# breakout-18.net
KiCad netlist of a schematic drawn in EAGLE
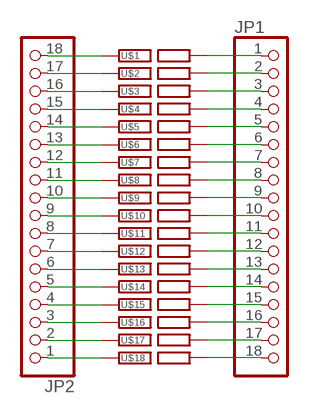
[diagram p0: schematic, sheet 1]

(export (version "E")
  (design (tool "Eeschema 10.0.6"))
  (components
    (comp (ref "JP1")
      (value "PINHD-1X18")
      (footprint "eagle-import:1X18")
      (libsource (lib "eagle-import") (part "PINHD-1X18"))
    )
    (comp (ref "JP2")
      (value "PINHD-1X18")
      (footprint "eagle-import:1X18")
      (libsource (lib "eagle-import") (part "PINHD-1X18"))
    )
    (comp (ref "U$1")
      (value "RAILSEP")
      (footprint "eagle-import:RAIL")
      (libsource (lib "eagle-import") (part "RAILSEP"))
    )
    (comp (ref "U$2")
      (value "RAILSEP")
      (footprint "eagle-import:RAIL")
      (libsource (lib "eagle-import") (part "RAILSEP"))
    )
    (comp (ref "U$3")
      (value "RAILSEP")
      (footprint "eagle-import:RAIL")
      (libsource (lib "eagle-import") (part "RAILSEP"))
    )
    (comp (ref "U$4")
      (value "RAILSEP")
      (footprint "eagle-import:RAIL")
      (libsource (lib "eagle-import") (part "RAILSEP"))
    )
    (comp (ref "U$5")
      (value "RAILSEP")
      (footprint "eagle-import:RAIL")
      (libsource (lib "eagle-import") (part "RAILSEP"))
    )
    (comp (ref "U$6")
      (value "RAILSEP")
      (footprint "eagle-import:RAIL")
      (libsource (lib "eagle-import") (part "RAILSEP"))
    )
    (comp (ref "U$7")
      (value "RAILSEP")
      (footprint "eagle-import:RAIL")
      (libsource (lib "eagle-import") (part "RAILSEP"))
    )
    (comp (ref "U$8")
      (value "RAILSEP")
      (footprint "eagle-import:RAIL")
      (libsource (lib "eagle-import") (part "RAILSEP"))
    )
    (comp (ref "U$9")
      (value "RAILSEP")
      (footprint "eagle-import:RAIL")
      (libsource (lib "eagle-import") (part "RAILSEP"))
    )
    (comp (ref "U$10")
      (value "RAILSEP")
      (footprint "eagle-import:RAIL")
      (libsource (lib "eagle-import") (part "RAILSEP"))
    )
    (comp (ref "U$11")
      (value "RAILSEP")
      (footprint "eagle-import:RAIL")
      (libsource (lib "eagle-import") (part "RAILSEP"))
    )
    (comp (ref "U$12")
      (value "RAILSEP")
      (footprint "eagle-import:RAIL")
      (libsource (lib "eagle-import") (part "RAILSEP"))
    )
    (comp (ref "U$13")
      (value "RAILSEP")
      (footprint "eagle-import:RAIL")
      (libsource (lib "eagle-import") (part "RAILSEP"))
    )
    (comp (ref "U$14")
      (value "RAILSEP")
      (footprint "eagle-import:RAIL")
      (libsource (lib "eagle-import") (part "RAILSEP"))
    )
    (comp (ref "U$15")
      (value "RAILSEP")
      (footprint "eagle-import:RAIL")
      (libsource (lib "eagle-import") (part "RAILSEP"))
    )
    (comp (ref "U$16")
      (value "RAILSEP")
      (footprint "eagle-import:RAIL")
      (libsource (lib "eagle-import") (part "RAILSEP"))
    )
    (comp (ref "U$17")
      (value "RAILSEP")
      (footprint "eagle-import:RAIL")
      (libsource (lib "eagle-import") (part "RAILSEP"))
    )
    (comp (ref "U$18")
      (value "RAILSEP")
      (footprint "eagle-import:RAIL")
      (libsource (lib "eagle-import") (part "RAILSEP"))
    )
  )
  (nets
    (net (code "1") (name "Net-(U$1-L)") (class "Default")
      (node (ref "JP2") (pin "18") (pinfunction "18_18") (pintype "passive"))
      (node (ref "U$1") (pin "P$L") (pinfunction "L_P$L") (pintype "bidirectional"))
    )
    (net (code "2") (name "Net-(U$1-R)") (class "Default")
      (node (ref "JP1") (pin "1") (pinfunction "1_1") (pintype "passive"))
      (node (ref "U$1") (pin "P$R") (pinfunction "R_P$R") (pintype "bidirectional"))
    )
    (net (code "3") (name "Net-(U$2-L)") (class "Default")
      (node (ref "JP2") (pin "17") (pinfunction "17_17") (pintype "passive"))
      (node (ref "U$2") (pin "P$L") (pinfunction "L_P$L") (pintype "bidirectional"))
    )
    (net (code "4") (name "Net-(U$2-R)") (class "Default")
      (node (ref "JP1") (pin "2") (pinfunction "2_2") (pintype "passive"))
      (node (ref "U$2") (pin "P$R") (pinfunction "R_P$R") (pintype "bidirectional"))
    )
    (net (code "5") (name "Net-(U$3-L)") (class "Default")
      (node (ref "JP2") (pin "16") (pinfunction "16_16") (pintype "passive"))
      (node (ref "U$3") (pin "P$L") (pinfunction "L_P$L") (pintype "bidirectional"))
    )
    (net (code "6") (name "Net-(U$3-R)") (class "Default")
      (node (ref "JP1") (pin "3") (pinfunction "3_3") (pintype "passive"))
      (node (ref "U$3") (pin "P$R") (pinfunction "R_P$R") (pintype "bidirectional"))
    )
    (net (code "7") (name "Net-(U$4-L)") (class "Default")
      (node (ref "JP2") (pin "15") (pinfunction "15_15") (pintype "passive"))
      (node (ref "U$4") (pin "P$L") (pinfunction "L_P$L") (pintype "bidirectional"))
    )
    (net (code "8") (name "Net-(U$4-R)") (class "Default")
      (node (ref "JP1") (pin "4") (pinfunction "4_4") (pintype "passive"))
      (node (ref "U$4") (pin "P$R") (pinfunction "R_P$R") (pintype "bidirectional"))
    )
    (net (code "9") (name "Net-(U$5-L)") (class "Default")
      (node (ref "JP2") (pin "14") (pinfunction "14_14") (pintype "passive"))
      (node (ref "U$5") (pin "P$L") (pinfunction "L_P$L") (pintype "bidirectional"))
    )
    (net (code "10") (name "Net-(U$5-R)") (class "Default")
      (node (ref "JP1") (pin "5") (pinfunction "5_5") (pintype "passive"))
      (node (ref "U$5") (pin "P$R") (pinfunction "R_P$R") (pintype "bidirectional"))
    )
    (net (code "11") (name "Net-(U$6-L)") (class "Default")
      (node (ref "JP2") (pin "13") (pinfunction "13_13") (pintype "passive"))
      (node (ref "U$6") (pin "P$L") (pinfunction "L_P$L") (pintype "bidirectional"))
    )
    (net (code "12") (name "Net-(U$6-R)") (class "Default")
      (node (ref "JP1") (pin "6") (pinfunction "6_6") (pintype "passive"))
      (node (ref "U$6") (pin "P$R") (pinfunction "R_P$R") (pintype "bidirectional"))
    )
    (net (code "13") (name "Net-(U$7-L)") (class "Default")
      (node (ref "JP2") (pin "12") (pinfunction "12_12") (pintype "passive"))
      (node (ref "U$7") (pin "P$L") (pinfunction "L_P$L") (pintype "bidirectional"))
    )
    (net (code "14") (name "Net-(U$7-R)") (class "Default")
      (node (ref "JP1") (pin "7") (pinfunction "7_7") (pintype "passive"))
      (node (ref "U$7") (pin "P$R") (pinfunction "R_P$R") (pintype "bidirectional"))
    )
    (net (code "15") (name "Net-(U$8-L)") (class "Default")
      (node (ref "JP2") (pin "11") (pinfunction "11_11") (pintype "passive"))
      (node (ref "U$8") (pin "P$L") (pinfunction "L_P$L") (pintype "bidirectional"))
    )
    (net (code "16") (name "Net-(U$8-R)") (class "Default")
      (node (ref "JP1") (pin "8") (pinfunction "8_8") (pintype "passive"))
      (node (ref "U$8") (pin "P$R") (pinfunction "R_P$R") (pintype "bidirectional"))
    )
    (net (code "17") (name "Net-(U$9-L)") (class "Default")
      (node (ref "JP2") (pin "10") (pinfunction "10_10") (pintype "passive"))
      (node (ref "U$9") (pin "P$L") (pinfunction "L_P$L") (pintype "bidirectional"))
    )
    (net (code "18") (name "Net-(U$9-R)") (class "Default")
      (node (ref "JP1") (pin "9") (pinfunction "9_9") (pintype "passive"))
      (node (ref "U$9") (pin "P$R") (pinfunction "R_P$R") (pintype "bidirectional"))
    )
    (net (code "19") (name "Net-(U$10-L)") (class "Default")
      (node (ref "JP2") (pin "9") (pinfunction "9_9") (pintype "passive"))
      (node (ref "U$10") (pin "P$L") (pinfunction "L_P$L") (pintype "bidirectional"))
    )
    (net (code "20") (name "Net-(U$10-R)") (class "Default")
      (node (ref "JP1") (pin "10") (pinfunction "10_10") (pintype "passive"))
      (node (ref "U$10") (pin "P$R") (pinfunction "R_P$R") (pintype "bidirectional"))
    )
    (net (code "21") (name "Net-(U$11-L)") (class "Default")
      (node (ref "JP2") (pin "8") (pinfunction "8_8") (pintype "passive"))
      (node (ref "U$11") (pin "P$L") (pinfunction "L_P$L") (pintype "bidirectional"))
    )
    (net (code "22") (name "Net-(U$11-R)") (class "Default")
      (node (ref "JP1") (pin "11") (pinfunction "11_11") (pintype "passive"))
      (node (ref "U$11") (pin "P$R") (pinfunction "R_P$R") (pintype "bidirectional"))
    )
    (net (code "23") (name "Net-(U$12-L)") (class "Default")
      (node (ref "JP2") (pin "7") (pinfunction "7_7") (pintype "passive"))
      (node (ref "U$12") (pin "P$L") (pinfunction "L_P$L") (pintype "bidirectional"))
    )
    (net (code "24") (name "Net-(U$12-R)") (class "Default")
      (node (ref "JP1") (pin "12") (pinfunction "12_12") (pintype "passive"))
      (node (ref "U$12") (pin "P$R") (pinfunction "R_P$R") (pintype "bidirectional"))
    )
    (net (code "25") (name "Net-(U$13-L)") (class "Default")
      (node (ref "JP2") (pin "6") (pinfunction "6_6") (pintype "passive"))
      (node (ref "U$13") (pin "P$L") (pinfunction "L_P$L") (pintype "bidirectional"))
    )
    (net (code "26") (name "Net-(U$13-R)") (class "Default")
      (node (ref "JP1") (pin "13") (pinfunction "13_13") (pintype "passive"))
      (node (ref "U$13") (pin "P$R") (pinfunction "R_P$R") (pintype "bidirectional"))
    )
    (net (code "27") (name "Net-(U$14-L)") (class "Default")
      (node (ref "JP2") (pin "5") (pinfunction "5_5") (pintype "passive"))
      (node (ref "U$14") (pin "P$L") (pinfunction "L_P$L") (pintype "bidirectional"))
    )
    (net (code "28") (name "Net-(U$14-R)") (class "Default")
      (node (ref "JP1") (pin "14") (pinfunction "14_14") (pintype "passive"))
      (node (ref "U$14") (pin "P$R") (pinfunction "R_P$R") (pintype "bidirectional"))
    )
    (net (code "29") (name "Net-(U$15-L)") (class "Default")
      (node (ref "JP2") (pin "4") (pinfunction "4_4") (pintype "passive"))
      (node (ref "U$15") (pin "P$L") (pinfunction "L_P$L") (pintype "bidirectional"))
    )
    (net (code "30") (name "Net-(U$15-R)") (class "Default")
      (node (ref "JP1") (pin "15") (pinfunction "15_15") (pintype "passive"))
      (node (ref "U$15") (pin "P$R") (pinfunction "R_P$R") (pintype "bidirectional"))
    )
    (net (code "31") (name "Net-(U$16-L)") (class "Default")
      (node (ref "JP2") (pin "3") (pinfunction "3_3") (pintype "passive"))
      (node (ref "U$16") (pin "P$L") (pinfunction "L_P$L") (pintype "bidirectional"))
    )
    (net (code "32") (name "Net-(U$16-R)") (class "Default")
      (node (ref "JP1") (pin "16") (pinfunction "16_16") (pintype "passive"))
      (node (ref "U$16") (pin "P$R") (pinfunction "R_P$R") (pintype "bidirectional"))
    )
    (net (code "33") (name "Net-(U$17-L)") (class "Default")
      (node (ref "JP2") (pin "2") (pinfunction "2_2") (pintype "passive"))
      (node (ref "U$17") (pin "P$L") (pinfunction "L_P$L") (pintype "bidirectional"))
    )
    (net (code "34") (name "Net-(U$17-R)") (class "Default")
      (node (ref "JP1") (pin "17") (pinfunction "17_17") (pintype "passive"))
      (node (ref "U$17") (pin "P$R") (pinfunction "R_P$R") (pintype "bidirectional"))
    )
    (net (code "35") (name "Net-(U$18-L)") (class "Default")
      (node (ref "JP2") (pin "1") (pinfunction "1_1") (pintype "passive"))
      (node (ref "U$18") (pin "P$L") (pinfunction "L_P$L") (pintype "bidirectional"))
    )
    (net (code "36") (name "Net-(U$18-R)") (class "Default")
      (node (ref "JP1") (pin "18") (pinfunction "18_18") (pintype "passive"))
      (node (ref "U$18") (pin "P$R") (pinfunction "R_P$R") (pintype "bidirectional"))
    )
  )
)
